# 2164_svf_single_plane_smd.net
KiCad netlist of a schematic drawn in EAGLE
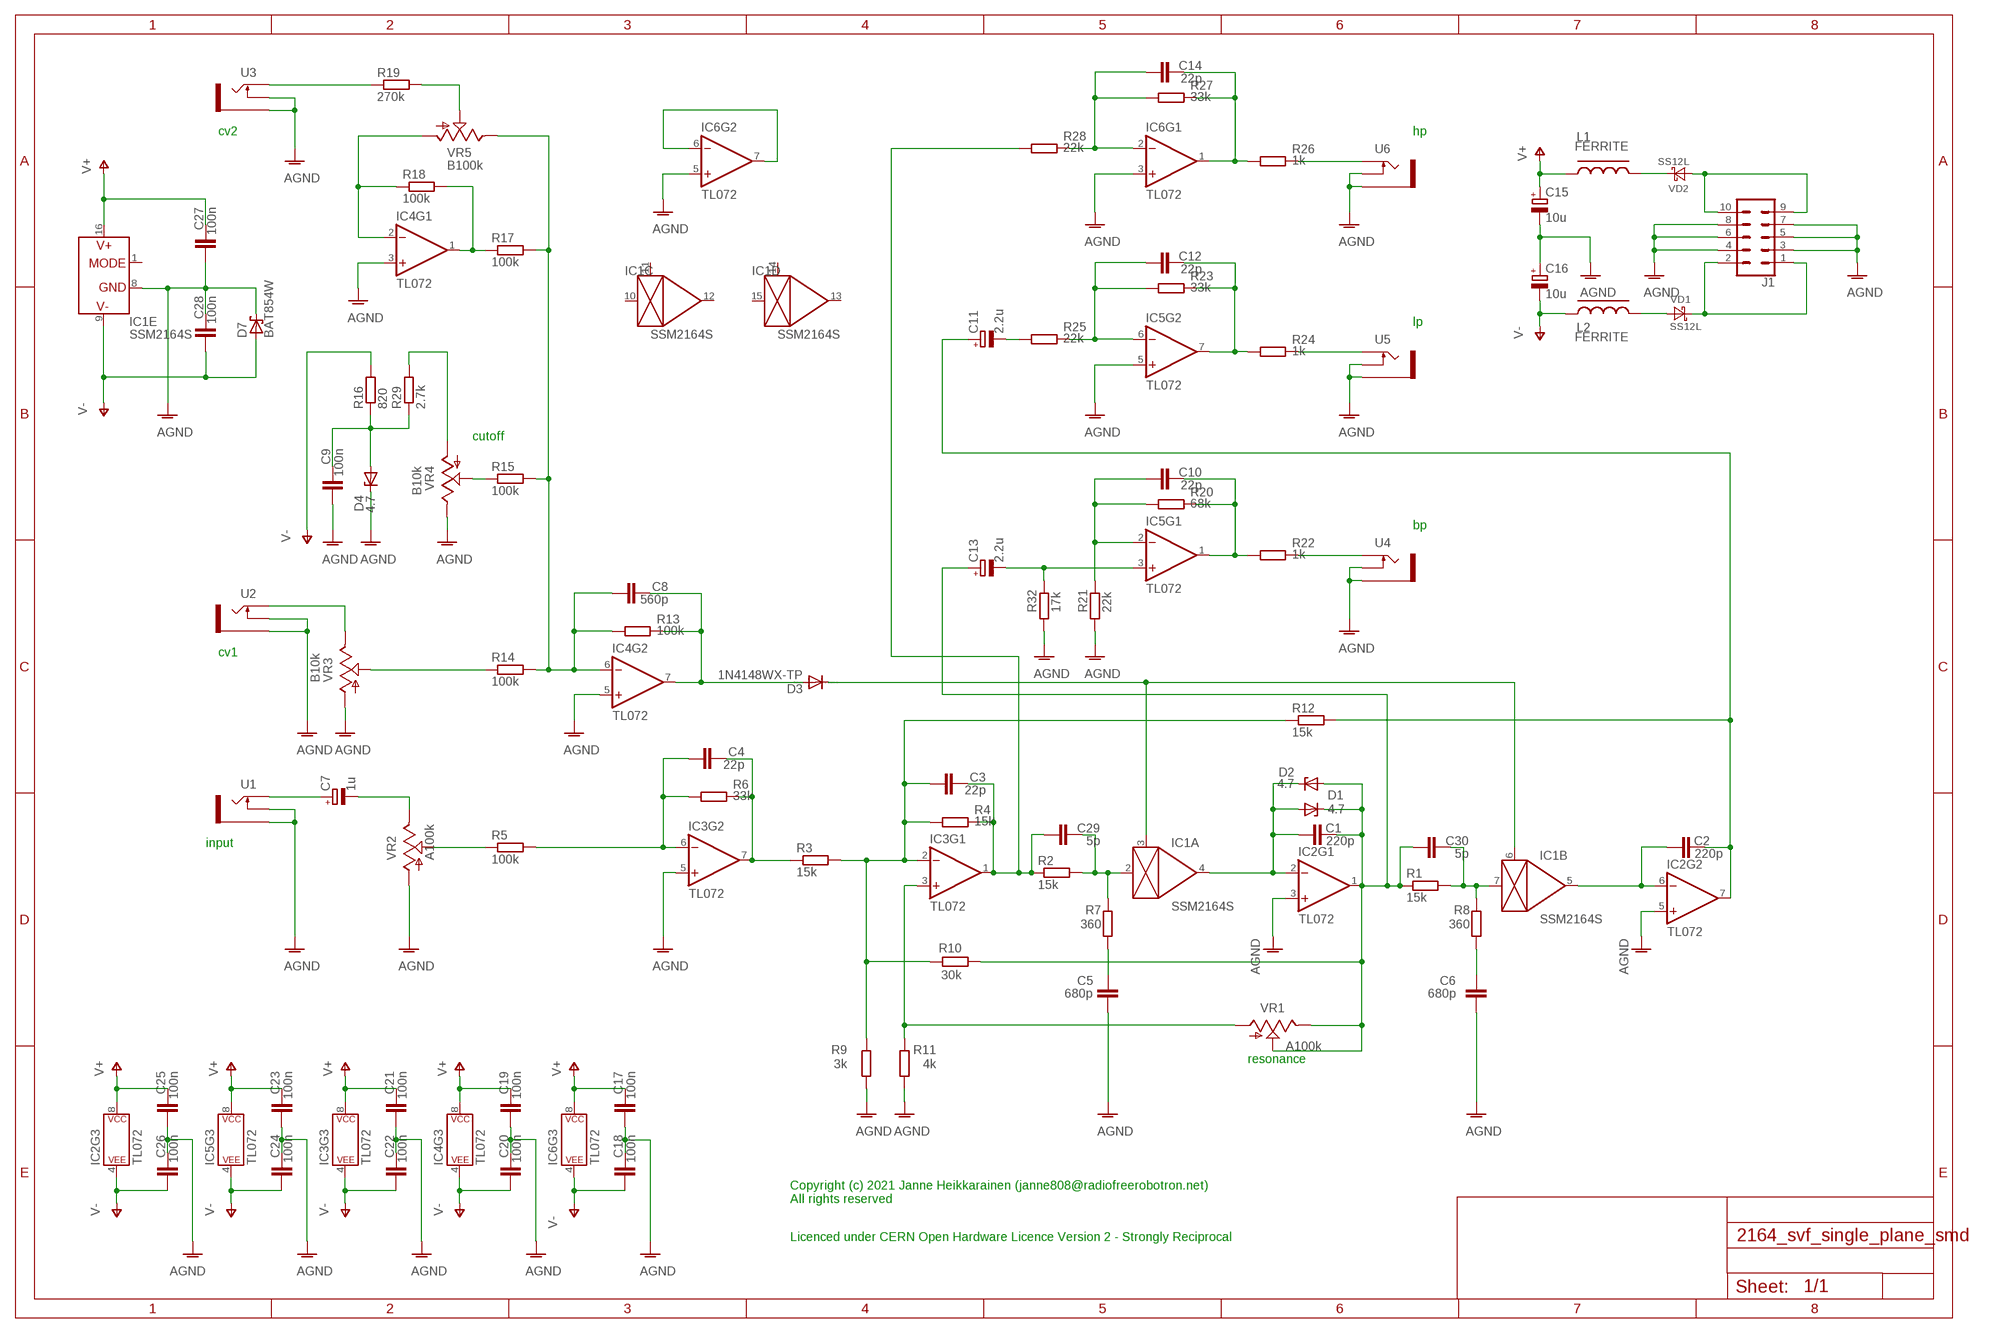
[diagram p0: schematic, sheet 1]

(export (version "E")
  (design (tool "Eeschema 10.0.6"))
  (components
    (comp (ref "C1")
      (value "220p")
      (footprint "eagle-import:C0603")
      (libsource (lib "eagle-import") (part "C-EUC0603"))
    )
    (comp (ref "C2")
      (value "220p")
      (footprint "eagle-import:C0603")
      (libsource (lib "eagle-import") (part "C-EUC0603"))
    )
    (comp (ref "C3")
      (value "22p")
      (footprint "eagle-import:C0603")
      (libsource (lib "eagle-import") (part "C-EUC0603"))
    )
    (comp (ref "C4")
      (value "22p")
      (footprint "eagle-import:C0603")
      (libsource (lib "eagle-import") (part "C-EUC0603"))
    )
    (comp (ref "C5")
      (value "680p")
      (footprint "eagle-import:C0603")
      (libsource (lib "eagle-import") (part "C-EUC0603"))
    )
    (comp (ref "C6")
      (value "680p")
      (footprint "eagle-import:C0603")
      (libsource (lib "eagle-import") (part "C-EUC0603"))
    )
    (comp (ref "C7")
      (value "1u")
      (footprint "eagle-import:PANASONIC_B")
      (libsource (lib "eagle-import") (part "CPOL-EUB"))
    )
    (comp (ref "C8")
      (value "560p")
      (footprint "eagle-import:C0603")
      (libsource (lib "eagle-import") (part "C-EUC0603"))
    )
    (comp (ref "C9")
      (value "100n")
      (footprint "eagle-import:C0603")
      (libsource (lib "eagle-import") (part "C-EUC0603"))
    )
    (comp (ref "C10")
      (value "22p")
      (footprint "eagle-import:C0603")
      (libsource (lib "eagle-import") (part "C-EUC0603"))
    )
    (comp (ref "C11")
      (value "2.2u")
      (footprint "eagle-import:PANASONIC_B")
      (libsource (lib "eagle-import") (part "CPOL-EUB"))
    )
    (comp (ref "C12")
      (value "22p")
      (footprint "eagle-import:C0603")
      (libsource (lib "eagle-import") (part "C-EUC0603"))
    )
    (comp (ref "C13")
      (value "2.2u")
      (footprint "eagle-import:PANASONIC_B")
      (libsource (lib "eagle-import") (part "CPOL-EUB"))
    )
    (comp (ref "C14")
      (value "22p")
      (footprint "eagle-import:C0603")
      (libsource (lib "eagle-import") (part "C-EUC0603"))
    )
    (comp (ref "C15")
      (value "10u")
      (footprint "eagle-import:PANASONIC_B")
      (libsource (lib "eagle-import") (part "CPOL-EUB"))
    )
    (comp (ref "C16")
      (value "10u")
      (footprint "eagle-import:PANASONIC_B")
      (libsource (lib "eagle-import") (part "CPOL-EUB"))
    )
    (comp (ref "C17")
      (value "100n")
      (footprint "eagle-import:C0603")
      (libsource (lib "eagle-import") (part "C-EUC0603"))
    )
    (comp (ref "C18")
      (value "100n")
      (footprint "eagle-import:C0603")
      (libsource (lib "eagle-import") (part "C-EUC0603"))
    )
    (comp (ref "C19")
      (value "100n")
      (footprint "eagle-import:C0603")
      (libsource (lib "eagle-import") (part "C-EUC0603"))
    )
    (comp (ref "C20")
      (value "100n")
      (footprint "eagle-import:C0603")
      (libsource (lib "eagle-import") (part "C-EUC0603"))
    )
    (comp (ref "C21")
      (value "100n")
      (footprint "eagle-import:C0603")
      (libsource (lib "eagle-import") (part "C-EUC0603"))
    )
    (comp (ref "C22")
      (value "100n")
      (footprint "eagle-import:C0603")
      (libsource (lib "eagle-import") (part "C-EUC0603"))
    )
    (comp (ref "C23")
      (value "100n")
      (footprint "eagle-import:C0603")
      (libsource (lib "eagle-import") (part "C-EUC0603"))
    )
    (comp (ref "C24")
      (value "100n")
      (footprint "eagle-import:C0603")
      (libsource (lib "eagle-import") (part "C-EUC0603"))
    )
    (comp (ref "C25")
      (value "100n")
      (footprint "eagle-import:C0603")
      (libsource (lib "eagle-import") (part "C-EUC0603"))
    )
    (comp (ref "C26")
      (value "100n")
      (footprint "eagle-import:C0603")
      (libsource (lib "eagle-import") (part "C-EUC0603"))
    )
    (comp (ref "C27")
      (value "100n")
      (footprint "eagle-import:C0603")
      (libsource (lib "eagle-import") (part "C-EUC0603"))
    )
    (comp (ref "C28")
      (value "100n")
      (footprint "eagle-import:C0603")
      (libsource (lib "eagle-import") (part "C-EUC0603"))
    )
    (comp (ref "C29")
      (value "5p")
      (footprint "eagle-import:C0603")
      (libsource (lib "eagle-import") (part "C-EUC0603"))
    )
    (comp (ref "C30")
      (value "5p")
      (footprint "eagle-import:C0603")
      (libsource (lib "eagle-import") (part "C-EUC0603"))
    )
    (comp (ref "D1")
      (value "4.7")
      (footprint "eagle-import:DIODE_SOD80C")
      (libsource (lib "eagle-import") (part "DIODE_ZENER-DIODESOD80C"))
    )
    (comp (ref "D2")
      (value "4.7")
      (footprint "eagle-import:DIODE_SOD80C")
      (libsource (lib "eagle-import") (part "DIODE_ZENER-DIODESOD80C"))
    )
    (comp (ref "D3")
      (value "1N4148WX-TP")
      (footprint "eagle-import:SOD323R-INFINEON")
      (libsource (lib "eagle-import") (part "1N4148WX-TP"))
    )
    (comp (ref "D4")
      (value "4.7")
      (footprint "eagle-import:DIODE_SOD80C")
      (libsource (lib "eagle-import") (part "DIODE_ZENER-DIODESOD80C"))
    )
    (comp (ref "D7")
      (value "BAT854W")
      (footprint "eagle-import:SOT323")
      (libsource (lib "eagle-import") (part "1PS70SB10"))
    )
    (comp (ref "IC1")
      (value "SSM2164S")
      (footprint "eagle-import:SOIC16N")
      (libsource (lib "eagle-import") (part "SSM2164S"))
    )
    (comp (ref "IC2")
      (value "TL072")
      (footprint "eagle-import:SO08")
      (libsource (lib "eagle-import") (part "OPAMP-DUALU"))
    )
    (comp (ref "IC3")
      (value "TL072")
      (footprint "eagle-import:SO08")
      (libsource (lib "eagle-import") (part "OPAMP-DUALU"))
    )
    (comp (ref "IC4")
      (value "TL072")
      (footprint "eagle-import:SO08")
      (libsource (lib "eagle-import") (part "OPAMP-DUALU"))
    )
    (comp (ref "IC5")
      (value "TL072")
      (footprint "eagle-import:SO08")
      (libsource (lib "eagle-import") (part "OPAMP-DUALU"))
    )
    (comp (ref "IC6")
      (value "TL072")
      (footprint "eagle-import:SO08")
      (libsource (lib "eagle-import") (part "OPAMP-DUALU"))
    )
    (comp (ref "J1")
      (value "CONN_05X2SHD")
      (footprint "eagle-import:2X5-SHROUDED")
      (libsource (lib "eagle-import") (part "CONN_05X2SHD"))
    )
    (comp (ref "L1")
      (value "FERRITE")
      (footprint "eagle-import:0603")
      (fields (field (name "PARTNO") "?"))
      (libsource (lib "eagle-import") (part "EXC3BP"))
    )
    (comp (ref "L2")
      (value "FERRITE")
      (footprint "eagle-import:0603")
      (fields (field (name "PARTNO") "?"))
      (libsource (lib "eagle-import") (part "EXC3BP"))
    )
    (comp (ref "R1")
      (value "15k")
      (footprint "eagle-import:R0603")
      (libsource (lib "eagle-import") (part "R-EU_R0603"))
    )
    (comp (ref "R2")
      (value "15k")
      (footprint "eagle-import:R0603")
      (libsource (lib "eagle-import") (part "R-EU_R0603"))
    )
    (comp (ref "R3")
      (value "15k")
      (footprint "eagle-import:R0603")
      (libsource (lib "eagle-import") (part "R-EU_R0603"))
    )
    (comp (ref "R4")
      (value "15k")
      (footprint "eagle-import:R0603")
      (libsource (lib "eagle-import") (part "R-EU_R0603"))
    )
    (comp (ref "R5")
      (value "100k")
      (footprint "eagle-import:R0603")
      (libsource (lib "eagle-import") (part "R-EU_R0603"))
    )
    (comp (ref "R6")
      (value "33k")
      (footprint "eagle-import:R0603")
      (libsource (lib "eagle-import") (part "R-EU_R0603"))
    )
    (comp (ref "R7")
      (value "360")
      (footprint "eagle-import:R0603")
      (libsource (lib "eagle-import") (part "R-EU_R0603"))
    )
    (comp (ref "R8")
      (value "360")
      (footprint "eagle-import:R0603")
      (libsource (lib "eagle-import") (part "R-EU_R0603"))
    )
    (comp (ref "R9")
      (value "3k")
      (footprint "eagle-import:R0603")
      (libsource (lib "eagle-import") (part "R-EU_R0603"))
    )
    (comp (ref "R10")
      (value "30k")
      (footprint "eagle-import:R0603")
      (libsource (lib "eagle-import") (part "R-EU_R0603"))
    )
    (comp (ref "R11")
      (value "4k")
      (footprint "eagle-import:R0603")
      (libsource (lib "eagle-import") (part "R-EU_R0603"))
    )
    (comp (ref "R12")
      (value "15k")
      (footprint "eagle-import:R0603")
      (libsource (lib "eagle-import") (part "R-EU_R0603"))
    )
    (comp (ref "R13")
      (value "100k")
      (footprint "eagle-import:R0603")
      (libsource (lib "eagle-import") (part "R-EU_R0603"))
    )
    (comp (ref "R14")
      (value "100k")
      (footprint "eagle-import:R0603")
      (libsource (lib "eagle-import") (part "R-EU_R0603"))
    )
    (comp (ref "R15")
      (value "100k")
      (footprint "eagle-import:R0603")
      (libsource (lib "eagle-import") (part "R-EU_R0603"))
    )
    (comp (ref "R16")
      (value "820")
      (footprint "eagle-import:R0603")
      (libsource (lib "eagle-import") (part "R-EU_R0603"))
    )
    (comp (ref "R17")
      (value "100k")
      (footprint "eagle-import:R0603")
      (libsource (lib "eagle-import") (part "R-EU_R0603"))
    )
    (comp (ref "R18")
      (value "100k")
      (footprint "eagle-import:R0603")
      (libsource (lib "eagle-import") (part "R-EU_R0603"))
    )
    (comp (ref "R19")
      (value "270k")
      (footprint "eagle-import:R0603")
      (libsource (lib "eagle-import") (part "R-EU_R0603"))
    )
    (comp (ref "R20")
      (value "68k")
      (footprint "eagle-import:R0603")
      (libsource (lib "eagle-import") (part "R-EU_R0603"))
    )
    (comp (ref "R21")
      (value "22k")
      (footprint "eagle-import:R0603")
      (libsource (lib "eagle-import") (part "R-EU_R0603"))
    )
    (comp (ref "R22")
      (value "1k")
      (footprint "eagle-import:R0603")
      (libsource (lib "eagle-import") (part "R-EU_R0603"))
    )
    (comp (ref "R23")
      (value "33k")
      (footprint "eagle-import:R0603")
      (libsource (lib "eagle-import") (part "R-EU_R0603"))
    )
    (comp (ref "R24")
      (value "1k")
      (footprint "eagle-import:R0603")
      (libsource (lib "eagle-import") (part "R-EU_R0603"))
    )
    (comp (ref "R25")
      (value "22k")
      (footprint "eagle-import:R0603")
      (libsource (lib "eagle-import") (part "R-EU_R0603"))
    )
    (comp (ref "R26")
      (value "1k")
      (footprint "eagle-import:R0603")
      (libsource (lib "eagle-import") (part "R-EU_R0603"))
    )
    (comp (ref "R27")
      (value "33k")
      (footprint "eagle-import:R0603")
      (libsource (lib "eagle-import") (part "R-EU_R0603"))
    )
    (comp (ref "R28")
      (value "22k")
      (footprint "eagle-import:R0603")
      (libsource (lib "eagle-import") (part "R-EU_R0603"))
    )
    (comp (ref "R29")
      (value "2.7k")
      (footprint "eagle-import:R0603")
      (libsource (lib "eagle-import") (part "R-EU_R0603"))
    )
    (comp (ref "R32")
      (value "17k")
      (footprint "eagle-import:R0603")
      (libsource (lib "eagle-import") (part "R-EU_R0603"))
    )
    (comp (ref "U1")
      (value "THONKICONNNEW")
      (footprint "eagle-import:WQP-PJ301M-12_JACK")
      (libsource (lib "eagle-import") (part "THONKICONNNEW"))
    )
    (comp (ref "U2")
      (value "THONKICONNNEW")
      (footprint "eagle-import:WQP-PJ301M-12_JACK")
      (libsource (lib "eagle-import") (part "THONKICONNNEW"))
    )
    (comp (ref "U3")
      (value "THONKICONNNEW")
      (footprint "eagle-import:WQP-PJ301M-12_JACK")
      (libsource (lib "eagle-import") (part "THONKICONNNEW"))
    )
    (comp (ref "U4")
      (value "THONKICONNNEW")
      (footprint "eagle-import:WQP-PJ301M-12_JACK")
      (libsource (lib "eagle-import") (part "THONKICONNNEW"))
    )
    (comp (ref "U5")
      (value "THONKICONNNEW")
      (footprint "eagle-import:WQP-PJ301M-12_JACK")
      (libsource (lib "eagle-import") (part "THONKICONNNEW"))
    )
    (comp (ref "U6")
      (value "THONKICONNNEW")
      (footprint "eagle-import:WQP-PJ301M-12_JACK")
      (libsource (lib "eagle-import") (part "THONKICONNNEW"))
    )
    (comp (ref "VD1")
      (value "SS12L")
      (footprint "eagle-import:SMA")
      (libsource (lib "eagle-import") (part "DIODE-SCHOTTKY-SMA"))
    )
    (comp (ref "VD2")
      (value "SS12L")
      (footprint "eagle-import:SMA")
      (libsource (lib "eagle-import") (part "DIODE-SCHOTTKY-SMA"))
    )
    (comp (ref "VR1")
      (value "A100k")
      (footprint "eagle-import:9MM_SNAP-IN_POT")
      (libsource (lib "eagle-import") (part "9MM_SNAP-IN_POT_"))
    )
    (comp (ref "VR2")
      (value "A100k")
      (footprint "eagle-import:9MM_SNAP-IN_POT")
      (libsource (lib "eagle-import") (part "9MM_SNAP-IN_POT_"))
    )
    (comp (ref "VR3")
      (value "B10k")
      (footprint "eagle-import:9MM_SNAP-IN_POT")
      (libsource (lib "eagle-import") (part "9MM_SNAP-IN_POT_"))
    )
    (comp (ref "VR4")
      (value "B10k")
      (footprint "eagle-import:9MM_SNAP-IN_POT")
      (libsource (lib "eagle-import") (part "9MM_SNAP-IN_POT_"))
    )
    (comp (ref "VR5")
      (value "B100k")
      (footprint "eagle-import:9MM_SNAP-IN_POT")
      (libsource (lib "eagle-import") (part "9MM_SNAP-IN_POT_"))
    )
  )
  (nets
    (net (code "1") (name "AGND") (class "Default")
      (node (ref "C15") (pin "-") (pinfunction "-_-") (pintype "passive"))
      (node (ref "C16") (pin "+") (pinfunction "+_+") (pintype "passive"))
      (node (ref "C17") (pin "1") (pinfunction "1_1") (pintype "passive"))
      (node (ref "C18") (pin "2") (pinfunction "2_2") (pintype "passive"))
      (node (ref "C19") (pin "1") (pinfunction "1_1") (pintype "passive"))
      (node (ref "C20") (pin "2") (pinfunction "2_2") (pintype "passive"))
      (node (ref "C21") (pin "1") (pinfunction "1_1") (pintype "passive"))
      (node (ref "C22") (pin "2") (pinfunction "2_2") (pintype "passive"))
      (node (ref "C23") (pin "1") (pinfunction "1_1") (pintype "passive"))
      (node (ref "C24") (pin "2") (pinfunction "2_2") (pintype "passive"))
      (node (ref "C25") (pin "1") (pinfunction "1_1") (pintype "passive"))
      (node (ref "C26") (pin "2") (pinfunction "2_2") (pintype "passive"))
      (node (ref "C27") (pin "1") (pinfunction "1_1") (pintype "passive"))
      (node (ref "C28") (pin "2") (pinfunction "2_2") (pintype "passive"))
      (node (ref "C5") (pin "1") (pinfunction "1_1") (pintype "passive"))
      (node (ref "C6") (pin "1") (pinfunction "1_1") (pintype "passive"))
      (node (ref "C9") (pin "1") (pinfunction "1_1") (pintype "passive"))
      (node (ref "D4") (pin "C") (pinfunction "C_C") (pintype "passive"))
      (node (ref "D7") (pin "3") (pinfunction "K_3") (pintype "passive"))
      (node (ref "IC1") (pin "8") (pinfunction "GND_8") (pintype "power_in"))
      (node (ref "IC2") (pin "3") (pinfunction "+IN_3") (pintype "input"))
      (node (ref "IC2") (pin "5") (pinfunction "+IN_5") (pintype "input"))
      (node (ref "IC3") (pin "5") (pinfunction "+IN_5") (pintype "input"))
      (node (ref "IC4") (pin "3") (pinfunction "+IN_3") (pintype "input"))
      (node (ref "IC4") (pin "5") (pinfunction "+IN_5") (pintype "input"))
      (node (ref "IC5") (pin "5") (pinfunction "+IN_5") (pintype "input"))
      (node (ref "IC6") (pin "3") (pinfunction "+IN_3") (pintype "input"))
      (node (ref "IC6") (pin "5") (pinfunction "+IN_5") (pintype "input"))
      (node (ref "J1") (pin "3") (pinfunction "3_3") (pintype "passive"))
      (node (ref "J1") (pin "4") (pinfunction "4_4") (pintype "passive"))
      (node (ref "J1") (pin "5") (pinfunction "5_5") (pintype "passive"))
      (node (ref "J1") (pin "6") (pinfunction "6_6") (pintype "passive"))
      (node (ref "J1") (pin "7") (pinfunction "7_7") (pintype "passive"))
      (node (ref "J1") (pin "8") (pinfunction "8_8") (pintype "passive"))
      (node (ref "R11") (pin "1") (pinfunction "1_1") (pintype "passive"))
      (node (ref "R21") (pin "1") (pinfunction "1_1") (pintype "passive"))
      (node (ref "R32") (pin "1") (pinfunction "1_1") (pintype "passive"))
      (node (ref "R9") (pin "1") (pinfunction "1_1") (pintype "passive"))
      (node (ref "U1") (pin "P$2_SWITCH") (pinfunction "SWITCH_P$2_SWITCH") (pintype "passive"))
      (node (ref "U1") (pin "P$3_SLEEVE") (pinfunction "SLEEVE_P$3_SLEEVE") (pintype "passive"))
      (node (ref "U2") (pin "P$2_SWITCH") (pinfunction "SWITCH_P$2_SWITCH") (pintype "passive"))
      (node (ref "U2") (pin "P$3_SLEEVE") (pinfunction "SLEEVE_P$3_SLEEVE") (pintype "passive"))
      (node (ref "U3") (pin "P$2_SWITCH") (pinfunction "SWITCH_P$2_SWITCH") (pintype "passive"))
      (node (ref "U3") (pin "P$3_SLEEVE") (pinfunction "SLEEVE_P$3_SLEEVE") (pintype "passive"))
      (node (ref "U4") (pin "P$2_SWITCH") (pinfunction "SWITCH_P$2_SWITCH") (pintype "passive"))
      (node (ref "U4") (pin "P$3_SLEEVE") (pinfunction "SLEEVE_P$3_SLEEVE") (pintype "passive"))
      (node (ref "U5") (pin "P$2_SWITCH") (pinfunction "SWITCH_P$2_SWITCH") (pintype "passive"))
      (node (ref "U5") (pin "P$3_SLEEVE") (pinfunction "SLEEVE_P$3_SLEEVE") (pintype "passive"))
      (node (ref "U6") (pin "P$2_SWITCH") (pinfunction "SWITCH_P$2_SWITCH") (pintype "passive"))
      (node (ref "U6") (pin "P$3_SLEEVE") (pinfunction "SLEEVE_P$3_SLEEVE") (pintype "passive"))
      (node (ref "VR2") (pin "1") (pinfunction "A_1") (pintype "passive"))
      (node (ref "VR3") (pin "1") (pinfunction "A_1") (pintype "passive"))
      (node (ref "VR4") (pin "3") (pinfunction "E_3") (pintype "passive"))
    )
    (net (code "2") (name "Net-(C5-Pad2)") (class "Default")
      (node (ref "C5") (pin "2") (pinfunction "2_2") (pintype "passive"))
      (node (ref "R7") (pin "1") (pinfunction "1_1") (pintype "passive"))
    )
    (net (code "3") (name "Net-(C6-Pad2)") (class "Default")
      (node (ref "C6") (pin "2") (pinfunction "2_2") (pintype "passive"))
      (node (ref "R8") (pin "1") (pinfunction "1_1") (pintype "passive"))
    )
    (net (code "4") (name "Net-(C9-Pad2)") (class "Default")
      (node (ref "C9") (pin "2") (pinfunction "2_2") (pintype "passive"))
      (node (ref "D4") (pin "A") (pinfunction "A_A") (pintype "passive"))
      (node (ref "R16") (pin "1") (pinfunction "1_1") (pintype "passive"))
      (node (ref "R29") (pin "1") (pinfunction "1_1") (pintype "passive"))
    )
    (net (code "5") (name "Net-(C11-Pad-)") (class "Default")
      (node (ref "C11") (pin "-") (pinfunction "-_-") (pintype "passive"))
      (node (ref "R25") (pin "1") (pinfunction "1_1") (pintype "passive"))
    )
    (net (code "6") (name "Net-(IC1A-CTRL)") (class "Default")
      (node (ref "D3") (pin "C") (pinfunction "C_C") (pintype "passive"))
      (node (ref "IC1") (pin "3") (pinfunction "CTRL_3") (pintype "input"))
      (node (ref "IC1") (pin "6") (pinfunction "CTRL_6") (pintype "input"))
    )
    (net (code "7") (name "Net-(IC1A-IN)") (class "Default")
      (node (ref "C29") (pin "2") (pinfunction "2_2") (pintype "passive"))
      (node (ref "IC1") (pin "2") (pinfunction "IN_2") (pintype "input"))
      (node (ref "R2") (pin "2") (pinfunction "2_2") (pintype "passive"))
      (node (ref "R7") (pin "2") (pinfunction "2_2") (pintype "passive"))
    )
    (net (code "8") (name "Net-(IC1A-OUT)") (class "Default")
      (node (ref "C1") (pin "1") (pinfunction "1_1") (pintype "passive"))
      (node (ref "D1") (pin "A") (pinfunction "A_A") (pintype "passive"))
      (node (ref "D2") (pin "C") (pinfunction "C_C") (pintype "passive"))
      (node (ref "IC1") (pin "4") (pinfunction "OUT_4") (pintype "output"))
      (node (ref "IC2") (pin "2") (pinfunction "-IN_2") (pintype "input"))
    )
    (net (code "9") (name "Net-(IC1B-IN)") (class "Default")
      (node (ref "C30") (pin "2") (pinfunction "2_2") (pintype "passive"))
      (node (ref "IC1") (pin "7") (pinfunction "IN_7") (pintype "input"))
      (node (ref "R1") (pin "2") (pinfunction "2_2") (pintype "passive"))
      (node (ref "R8") (pin "2") (pinfunction "2_2") (pintype "passive"))
    )
    (net (code "10") (name "Net-(IC1B-OUT)") (class "Default")
      (node (ref "C2") (pin "1") (pinfunction "1_1") (pintype "passive"))
      (node (ref "IC1") (pin "5") (pinfunction "OUT_5") (pintype "output"))
      (node (ref "IC2") (pin "6") (pinfunction "-IN_6") (pintype "input"))
    )
    (net (code "11") (name "Net-(IC2A-OUT)") (class "Default")
      (node (ref "C1") (pin "2") (pinfunction "2_2") (pintype "passive"))
      (node (ref "C13") (pin "+") (pinfunction "+_+") (pintype "passive"))
      (node (ref "C30") (pin "1") (pinfunction "1_1") (pintype "passive"))
      (node (ref "D1") (pin "C") (pinfunction "C_C") (pintype "passive"))
      (node (ref "D2") (pin "A") (pinfunction "A_A") (pintype "passive"))
      (node (ref "IC2") (pin "1") (pinfunction "OUT_1") (pintype "output"))
      (node (ref "R1") (pin "1") (pinfunction "1_1") (pintype "passive"))
      (node (ref "R10") (pin "1") (pinfunction "1_1") (pintype "passive"))
      (node (ref "VR1") (pin "2") (pinfunction "S_2") (pintype "passive"))
      (node (ref "VR1") (pin "3") (pinfunction "E_3") (pintype "passive"))
    )
    (net (code "12") (name "Net-(IC2B-OUT)") (class "Default")
      (node (ref "C11") (pin "+") (pinfunction "+_+") (pintype "passive"))
      (node (ref "C2") (pin "2") (pinfunction "2_2") (pintype "passive"))
      (node (ref "IC2") (pin "7") (pinfunction "OUT_7") (pintype "output"))
      (node (ref "R12") (pin "2") (pinfunction "2_2") (pintype "passive"))
    )
    (net (code "13") (name "Net-(IC3A-+IN)") (class "Default")
      (node (ref "IC3") (pin "3") (pinfunction "+IN_3") (pintype "input"))
      (node (ref "R11") (pin "2") (pinfunction "2_2") (pintype "passive"))
      (node (ref "VR1") (pin "1") (pinfunction "A_1") (pintype "passive"))
    )
    (net (code "14") (name "Net-(IC3A--IN)") (class "Default")
      (node (ref "C3") (pin "1") (pinfunction "1_1") (pintype "passive"))
      (node (ref "IC3") (pin "2") (pinfunction "-IN_2") (pintype "input"))
      (node (ref "R10") (pin "2") (pinfunction "2_2") (pintype "passive"))
      (node (ref "R12") (pin "1") (pinfunction "1_1") (pintype "passive"))
      (node (ref "R3") (pin "2") (pinfunction "2_2") (pintype "passive"))
      (node (ref "R4") (pin "1") (pinfunction "1_1") (pintype "passive"))
      (node (ref "R9") (pin "2") (pinfunction "2_2") (pintype "passive"))
    )
    (net (code "15") (name "Net-(IC3A-OUT)") (class "Default")
      (node (ref "C29") (pin "1") (pinfunction "1_1") (pintype "passive"))
      (node (ref "C3") (pin "2") (pinfunction "2_2") (pintype "passive"))
      (node (ref "IC3") (pin "1") (pinfunction "OUT_1") (pintype "output"))
      (node (ref "R2") (pin "1") (pinfunction "1_1") (pintype "passive"))
      (node (ref "R28") (pin "1") (pinfunction "1_1") (pintype "passive"))
      (node (ref "R4") (pin "2") (pinfunction "2_2") (pintype "passive"))
    )
    (net (code "16") (name "Net-(IC3B--IN)") (class "Default")
      (node (ref "C4") (pin "1") (pinfunction "1_1") (pintype "passive"))
      (node (ref "IC3") (pin "6") (pinfunction "-IN_6") (pintype "input"))
      (node (ref "R5") (pin "2") (pinfunction "2_2") (pintype "passive"))
      (node (ref "R6") (pin "1") (pinfunction "1_1") (pintype "passive"))
    )
    (net (code "17") (name "Net-(IC3B-OUT)") (class "Default")
      (node (ref "C4") (pin "2") (pinfunction "2_2") (pintype "passive"))
      (node (ref "IC3") (pin "7") (pinfunction "OUT_7") (pintype "output"))
      (node (ref "R3") (pin "1") (pinfunction "1_1") (pintype "passive"))
      (node (ref "R6") (pin "2") (pinfunction "2_2") (pintype "passive"))
    )
    (net (code "18") (name "Net-(IC4A--IN)") (class "Default")
      (node (ref "IC4") (pin "2") (pinfunction "-IN_2") (pintype "input"))
      (node (ref "R18") (pin "1") (pinfunction "1_1") (pintype "passive"))
      (node (ref "VR5") (pin "1") (pinfunction "A_1") (pintype "passive"))
    )
    (net (code "19") (name "Net-(IC4A-OUT)") (class "Default")
      (node (ref "IC4") (pin "1") (pinfunction "OUT_1") (pintype "output"))
      (node (ref "R17") (pin "1") (pinfunction "1_1") (pintype "passive"))
      (node (ref "R18") (pin "2") (pinfunction "2_2") (pintype "passive"))
    )
    (net (code "20") (name "Net-(IC4B--IN)") (class "Default")
      (node (ref "C8") (pin "1") (pinfunction "1_1") (pintype "passive"))
      (node (ref "IC4") (pin "6") (pinfunction "-IN_6") (pintype "input"))
      (node (ref "R13") (pin "1") (pinfunction "1_1") (pintype "passive"))
      (node (ref "R14") (pin "2") (pinfunction "2_2") (pintype "passive"))
      (node (ref "R15") (pin "2") (pinfunction "2_2") (pintype "passive"))
      (node (ref "R17") (pin "2") (pinfunction "2_2") (pintype "passive"))
      (node (ref "VR5") (pin "3") (pinfunction "E_3") (pintype "passive"))
    )
    (net (code "21") (name "Net-(IC4B-OUT)") (class "Default")
      (node (ref "C8") (pin "2") (pinfunction "2_2") (pintype "passive"))
      (node (ref "D3") (pin "A") (pinfunction "A_A") (pintype "passive"))
      (node (ref "IC4") (pin "7") (pinfunction "OUT_7") (pintype "output"))
      (node (ref "R13") (pin "2") (pinfunction "2_2") (pintype "passive"))
    )
    (net (code "22") (name "Net-(IC5A-+IN)") (class "Default")
      (node (ref "C13") (pin "-") (pinfunction "-_-") (pintype "passive"))
      (node (ref "IC5") (pin "3") (pinfunction "+IN_3") (pintype "input"))
      (node (ref "R32") (pin "2") (pinfunction "2_2") (pintype "passive"))
    )
    (net (code "23") (name "Net-(IC5A--IN)") (class "Default")
      (node (ref "C10") (pin "1") (pinfunction "1_1") (pintype "passive"))
      (node (ref "IC5") (pin "2") (pinfunction "-IN_2") (pintype "input"))
      (node (ref "R20") (pin "1") (pinfunction "1_1") (pintype "passive"))
      (node (ref "R21") (pin "2") (pinfunction "2_2") (pintype "passive"))
    )
    (net (code "24") (name "Net-(IC5A-OUT)") (class "Default")
      (node (ref "C10") (pin "2") (pinfunction "2_2") (pintype "passive"))
      (node (ref "IC5") (pin "1") (pinfunction "OUT_1") (pintype "output"))
      (node (ref "R20") (pin "2") (pinfunction "2_2") (pintype "passive"))
      (node (ref "R22") (pin "1") (pinfunction "1_1") (pintype "passive"))
    )
    (net (code "25") (name "Net-(IC5B--IN)") (class "Default")
      (node (ref "C12") (pin "1") (pinfunction "1_1") (pintype "passive"))
      (node (ref "IC5") (pin "6") (pinfunction "-IN_6") (pintype "input"))
      (node (ref "R23") (pin "1") (pinfunction "1_1") (pintype "passive"))
      (node (ref "R25") (pin "2") (pinfunction "2_2") (pintype "passive"))
    )
    (net (code "26") (name "Net-(IC5B-OUT)") (class "Default")
      (node (ref "C12") (pin "2") (pinfunction "2_2") (pintype "passive"))
      (node (ref "IC5") (pin "7") (pinfunction "OUT_7") (pintype "output"))
      (node (ref "R23") (pin "2") (pinfunction "2_2") (pintype "passive"))
      (node (ref "R24") (pin "1") (pinfunction "1_1") (pintype "passive"))
    )
    (net (code "27") (name "Net-(IC6A--IN)") (class "Default")
      (node (ref "C14") (pin "1") (pinfunction "1_1") (pintype "passive"))
      (node (ref "IC6") (pin "2") (pinfunction "-IN_2") (pintype "input"))
      (node (ref "R27") (pin "1") (pinfunction "1_1") (pintype "passive"))
      (node (ref "R28") (pin "2") (pinfunction "2_2") (pintype "passive"))
    )
    (net (code "28") (name "Net-(IC6A-OUT)") (class "Default")
      (node (ref "C14") (pin "2") (pinfunction "2_2") (pintype "passive"))
      (node (ref "IC6") (pin "1") (pinfunction "OUT_1") (pintype "output"))
      (node (ref "R26") (pin "1") (pinfunction "1_1") (pintype "passive"))
      (node (ref "R27") (pin "2") (pinfunction "2_2") (pintype "passive"))
    )
    (net (code "29") (name "Net-(IC6B--IN)") (class "Default")
      (node (ref "IC6") (pin "6") (pinfunction "-IN_6") (pintype "input"))
      (node (ref "IC6") (pin "7") (pinfunction "OUT_7") (pintype "output"))
    )
    (net (code "30") (name "Net-(J1-Pad1)") (class "Default")
      (node (ref "J1") (pin "1") (pinfunction "1_1") (pintype "passive"))
      (node (ref "J1") (pin "2") (pinfunction "2_2") (pintype "passive"))
      (node (ref "VD1") (pin "C") (pinfunction "C_C") (pintype "passive"))
    )
    (net (code "31") (name "Net-(J1-Pad10)") (class "Default")
      (node (ref "J1") (pin "10") (pinfunction "10_10") (pintype "passive"))
      (node (ref "J1") (pin "9") (pinfunction "9_9") (pintype "passive"))
      (node (ref "VD2") (pin "A") (pinfunction "A_A") (pintype "passive"))
    )
    (net (code "32") (name "Net-(L1-Pad2)") (class "Default")
      (node (ref "L1") (pin "2") (pinfunction "2_2") (pintype "passive"))
      (node (ref "VD2") (pin "C") (pinfunction "C_C") (pintype "passive"))
    )
    (net (code "33") (name "Net-(L2-Pad2)") (class "Default")
      (node (ref "L2") (pin "2") (pinfunction "2_2") (pintype "passive"))
      (node (ref "VD1") (pin "A") (pinfunction "A_A") (pintype "passive"))
    )
    (net (code "34") (name "Net-(U1-TIP)") (class "Default")
      (node (ref "C7") (pin "+") (pinfunction "+_+") (pintype "passive"))
      (node (ref "U1") (pin "P$1_TIP") (pinfunction "TIP_P$1_TIP") (pintype "passive"))
    )
    (net (code "35") (name "Net-(U2-TIP)") (class "Default")
      (node (ref "U2") (pin "P$1_TIP") (pinfunction "TIP_P$1_TIP") (pintype "passive"))
      (node (ref "VR3") (pin "3") (pinfunction "E_3") (pintype "passive"))
    )
    (net (code "36") (name "Net-(U3-TIP)") (class "Default")
      (node (ref "R19") (pin "1") (pinfunction "1_1") (pintype "passive"))
      (node (ref "U3") (pin "P$1_TIP") (pinfunction "TIP_P$1_TIP") (pintype "passive"))
    )
    (net (code "37") (name "Net-(U4-TIP)") (class "Default")
      (node (ref "R22") (pin "2") (pinfunction "2_2") (pintype "passive"))
      (node (ref "U4") (pin "P$1_TIP") (pinfunction "TIP_P$1_TIP") (pintype "passive"))
    )
    (net (code "38") (name "Net-(U5-TIP)") (class "Default")
      (node (ref "R24") (pin "2") (pinfunction "2_2") (pintype "passive"))
      (node (ref "U5") (pin "P$1_TIP") (pinfunction "TIP_P$1_TIP") (pintype "passive"))
    )
    (net (code "39") (name "Net-(U6-TIP)") (class "Default")
      (node (ref "R26") (pin "2") (pinfunction "2_2") (pintype "passive"))
      (node (ref "U6") (pin "P$1_TIP") (pinfunction "TIP_P$1_TIP") (pintype "passive"))
    )
    (net (code "40") (name "Net-(VR2-E)") (class "Default")
      (node (ref "C7") (pin "-") (pinfunction "-_-") (pintype "passive"))
      (node (ref "VR2") (pin "3") (pinfunction "E_3") (pintype "passive"))
    )
    (net (code "41") (name "Net-(VR2-S)") (class "Default")
      (node (ref "R5") (pin "1") (pinfunction "1_1") (pintype "passive"))
      (node (ref "VR2") (pin "2") (pinfunction "S_2") (pintype "passive"))
    )
    (net (code "42") (name "Net-(VR3-S)") (class "Default")
      (node (ref "R14") (pin "1") (pinfunction "1_1") (pintype "passive"))
      (node (ref "VR3") (pin "2") (pinfunction "S_2") (pintype "passive"))
    )
    (net (code "43") (name "Net-(VR4-A)") (class "Default")
      (node (ref "R29") (pin "2") (pinfunction "2_2") (pintype "passive"))
      (node (ref "VR4") (pin "1") (pinfunction "A_1") (pintype "passive"))
    )
    (net (code "44") (name "Net-(VR4-S)") (class "Default")
      (node (ref "R15") (pin "1") (pinfunction "1_1") (pintype "passive"))
      (node (ref "VR4") (pin "2") (pinfunction "S_2") (pintype "passive"))
    )
    (net (code "45") (name "Net-(VR5-S)") (class "Default")
      (node (ref "R19") (pin "2") (pinfunction "2_2") (pintype "passive"))
      (node (ref "VR5") (pin "2") (pinfunction "S_2") (pintype "passive"))
    )
    (net (code "46") (name "V+") (class "Default")
      (node (ref "C15") (pin "+") (pinfunction "+_+") (pintype "passive"))
      (node (ref "C17") (pin "2") (pinfunction "2_2") (pintype "passive"))
      (node (ref "C19") (pin "2") (pinfunction "2_2") (pintype "passive"))
      (node (ref "C21") (pin "2") (pinfunction "2_2") (pintype "passive"))
      (node (ref "C23") (pin "2") (pinfunction "2_2") (pintype "passive"))
      (node (ref "C25") (pin "2") (pinfunction "2_2") (pintype "passive"))
      (node (ref "C27") (pin "2") (pinfunction "2_2") (pintype "passive"))
      (node (ref "IC1") (pin "16") (pinfunction "V+_16") (pintype "power_in"))
      (node (ref "IC2") (pin "8") (pinfunction "P$V+_8") (pintype "bidirectional"))
      (node (ref "IC3") (pin "8") (pinfunction "P$V+_8") (pintype "bidirectional"))
      (node (ref "IC4") (pin "8") (pinfunction "P$V+_8") (pintype "bidirectional"))
      (node (ref "IC5") (pin "8") (pinfunction "P$V+_8") (pintype "bidirectional"))
      (node (ref "IC6") (pin "8") (pinfunction "P$V+_8") (pintype "bidirectional"))
      (node (ref "L1") (pin "1") (pinfunction "1_1") (pintype "passive"))
    )
    (net (code "47") (name "V-") (class "Default")
      (node (ref "C16") (pin "-") (pinfunction "-_-") (pintype "passive"))
      (node (ref "C18") (pin "1") (pinfunction "1_1") (pintype "passive"))
      (node (ref "C20") (pin "1") (pinfunction "1_1") (pintype "passive"))
      (node (ref "C22") (pin "1") (pinfunction "1_1") (pintype "passive"))
      (node (ref "C24") (pin "1") (pinfunction "1_1") (pintype "passive"))
      (node (ref "C26") (pin "1") (pinfunction "1_1") (pintype "passive"))
      (node (ref "C28") (pin "1") (pinfunction "1_1") (pintype "passive"))
      (node (ref "D7") (pin "1") (pinfunction "A_1") (pintype "passive"))
      (node (ref "IC1") (pin "9") (pinfunction "V-_9") (pintype "power_in"))
      (node (ref "IC2") (pin "4") (pinfunction "P$V-_4") (pintype "bidirectional"))
      (node (ref "IC3") (pin "4") (pinfunction "P$V-_4") (pintype "bidirectional"))
      (node (ref "IC4") (pin "4") (pinfunction "P$V-_4") (pintype "bidirectional"))
      (node (ref "IC5") (pin "4") (pinfunction "P$V-_4") (pintype "bidirectional"))
      (node (ref "IC6") (pin "4") (pinfunction "P$V-_4") (pintype "bidirectional"))
      (node (ref "L2") (pin "1") (pinfunction "1_1") (pintype "passive"))
      (node (ref "R16") (pin "2") (pinfunction "2_2") (pintype "passive"))
    )
    (net (code "48") (name "unconnected-(IC1C-CTRL-Pad11)") (class "Default")
      (node (ref "IC1") (pin "11") (pinfunction "CTRL_11") (pintype "input"))
    )
    (net (code "49") (name "unconnected-(IC1C-IN-Pad10)") (class "Default")
      (node (ref "IC1") (pin "10") (pinfunction "IN_10") (pintype "input"))
    )
    (net (code "50") (name "unconnected-(IC1C-OUT-Pad12)") (class "Default")
      (node (ref "IC1") (pin "12") (pinfunction "OUT_12") (pintype "output"))
    )
    (net (code "51") (name "unconnected-(IC1D-CTRL-Pad14)") (class "Default")
      (node (ref "IC1") (pin "14") (pinfunction "CTRL_14") (pintype "input"))
    )
    (net (code "52") (name "unconnected-(IC1D-IN-Pad15)") (class "Default")
      (node (ref "IC1") (pin "15") (pinfunction "IN_15") (pintype "input"))
    )
    (net (code "53") (name "unconnected-(IC1D-OUT-Pad13)") (class "Default")
      (node (ref "IC1") (pin "13") (pinfunction "OUT_13") (pintype "output"))
    )
    (net (code "54") (name "unconnected-(IC1E-MODE-Pad1)") (class "Default")
      (node (ref "IC1") (pin "1") (pinfunction "MODE_1") (pintype "input"))
    )
  )
)
